# LCD_Daughterboard_v1_0.net
KiCad netlist of a schematic drawn in EAGLE
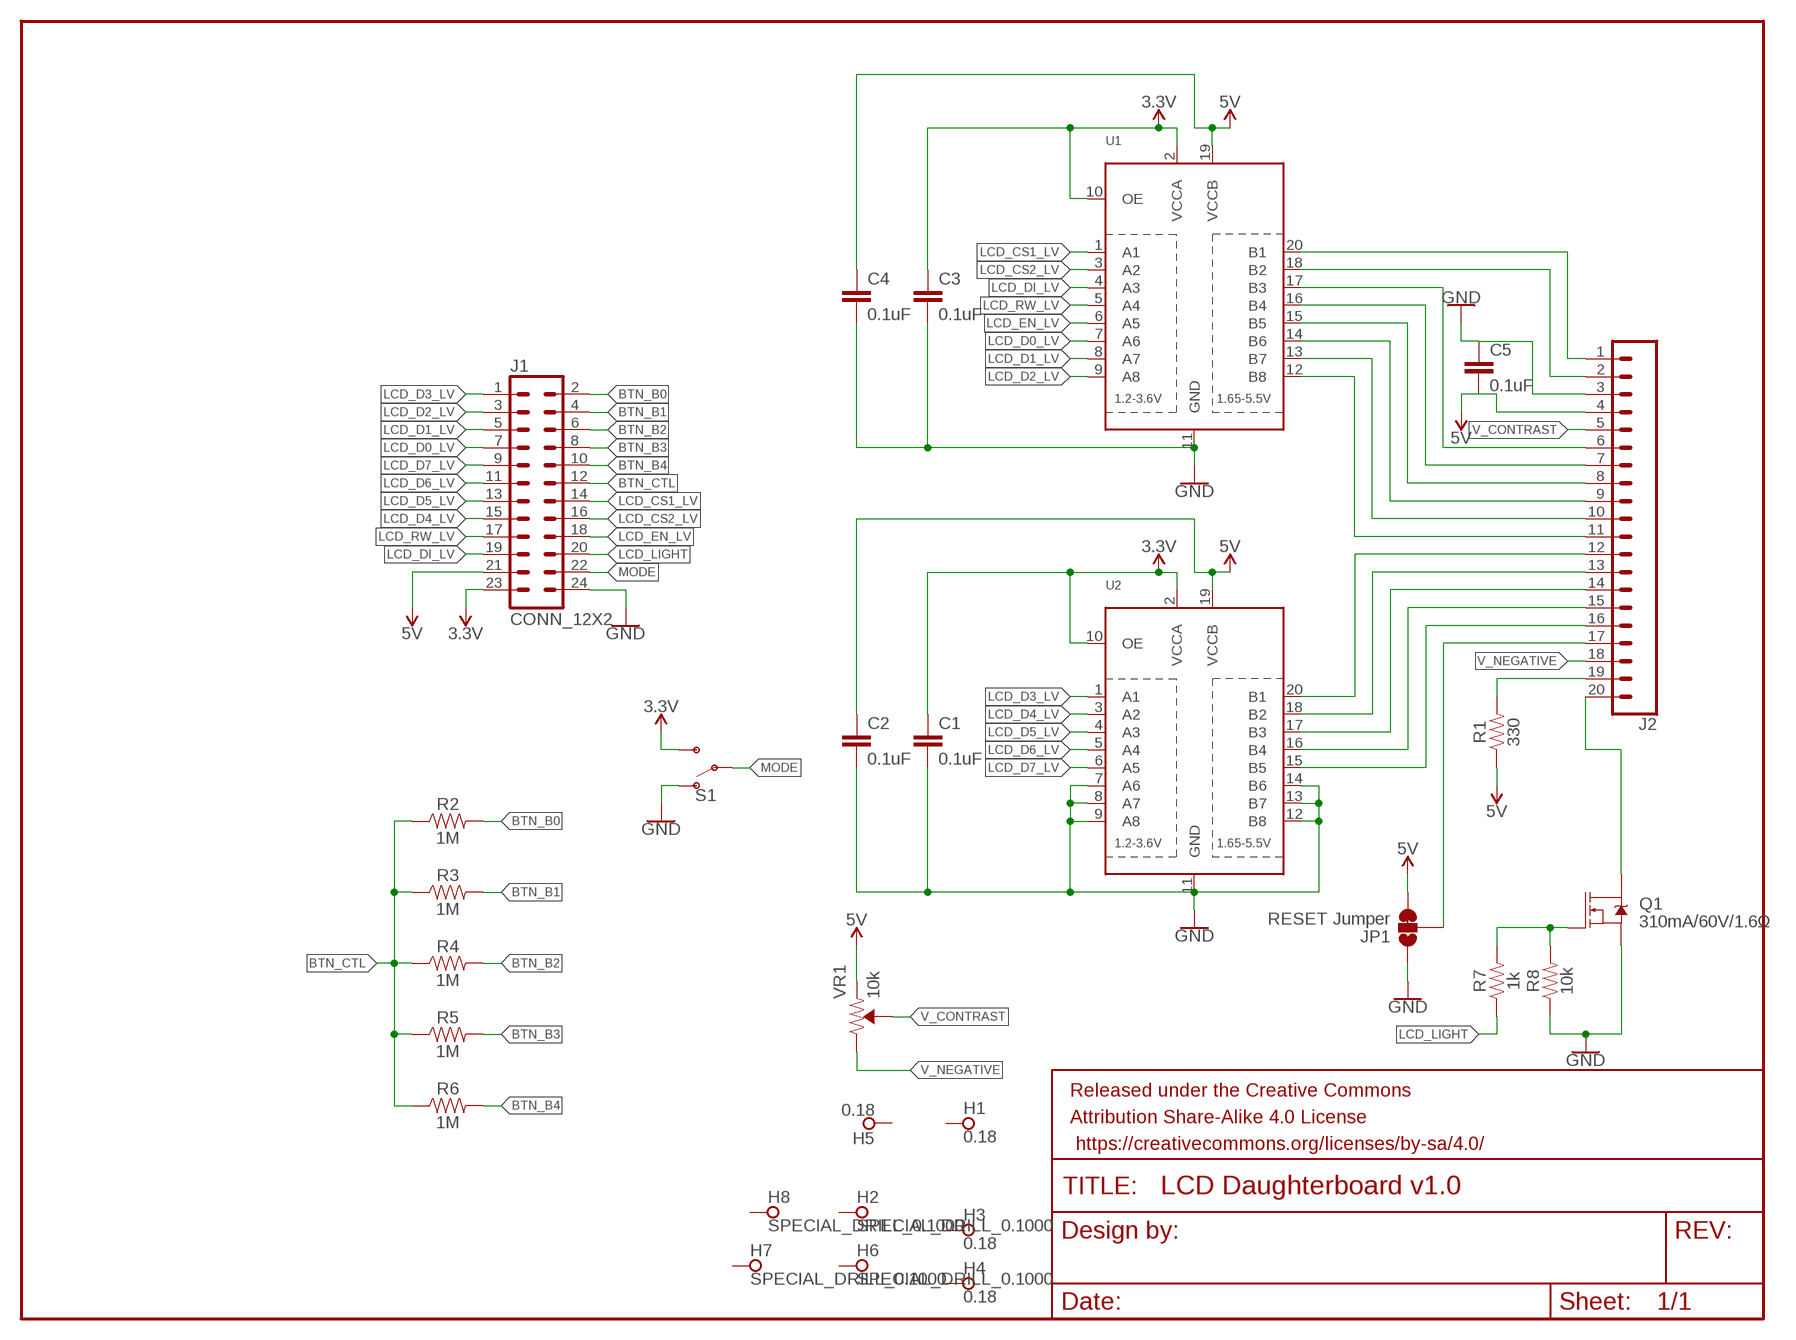
[diagram p0: schematic, sheet 1]

(export (version "E")
  (design (tool "Eeschema 10.0.6"))
  (components
    (comp (ref "C1")
      (value "0.1uF")
      (footprint "eagle-import:0603")
      (libsource (lib "eagle-import") (part "0.1UF-0603-25V-(+80/-20%)"))
    )
    (comp (ref "C2")
      (value "0.1uF")
      (footprint "eagle-import:0603")
      (libsource (lib "eagle-import") (part "0.1UF-0603-25V-(+80/-20%)"))
    )
    (comp (ref "C3")
      (value "0.1uF")
      (footprint "eagle-import:0603")
      (libsource (lib "eagle-import") (part "0.1UF-0603-25V-(+80/-20%)"))
    )
    (comp (ref "C4")
      (value "0.1uF")
      (footprint "eagle-import:0603")
      (libsource (lib "eagle-import") (part "0.1UF-0603-25V-(+80/-20%)"))
    )
    (comp (ref "C5")
      (value "0.1uF")
      (footprint "eagle-import:0603")
      (libsource (lib "eagle-import") (part "0.1UF-0603-25V-(+80/-20%)"))
    )
    (comp (ref "FRAME1")
      (value "FRAME-LETTERNO_PACKAGE")
      (footprint "eagle-import:DUMMY")
      (fields (field (name "DESIGNER") "Nobody"))
      (libsource (lib "eagle-import") (part "FRAME-LETTERNO_PACKAGE"))
    )
    (comp (ref "H1")
      (value "0.18")
      (footprint "eagle-import:PAD_0.1800")
      (libsource (lib "eagle-import") (part "SPECIAL_DRILL_0.1800"))
    )
    (comp (ref "H2")
      (value "SPECIAL_DRILL_0.1000")
      (footprint "eagle-import:PAD_0.1000")
      (libsource (lib "eagle-import") (part "SPECIAL_DRILL_0.1000"))
    )
    (comp (ref "H3")
      (value "0.18")
      (footprint "eagle-import:PAD_0.1800")
      (libsource (lib "eagle-import") (part "SPECIAL_DRILL_0.1800"))
    )
    (comp (ref "H4")
      (value "0.18")
      (footprint "eagle-import:PAD_0.1800")
      (libsource (lib "eagle-import") (part "SPECIAL_DRILL_0.1800"))
    )
    (comp (ref "H5")
      (value "0.18")
      (footprint "eagle-import:PAD_0.1800")
      (libsource (lib "eagle-import") (part "SPECIAL_DRILL_0.1800"))
    )
    (comp (ref "H6")
      (value "SPECIAL_DRILL_0.1000")
      (footprint "eagle-import:PAD_0.1000")
      (libsource (lib "eagle-import") (part "SPECIAL_DRILL_0.1000"))
    )
    (comp (ref "H7")
      (value "SPECIAL_DRILL_0.1000")
      (footprint "eagle-import:PAD_0.1000")
      (libsource (lib "eagle-import") (part "SPECIAL_DRILL_0.1000"))
    )
    (comp (ref "H8")
      (value "SPECIAL_DRILL_0.1000")
      (footprint "eagle-import:PAD_0.1000")
      (libsource (lib "eagle-import") (part "SPECIAL_DRILL_0.1000"))
    )
    (comp (ref "J1")
      (value "CONN_12X2")
      (footprint "eagle-import:2X12")
      (libsource (lib "eagle-import") (part "CONN_12X2"))
    )
    (comp (ref "J2")
      (value "CONN_20LOCK")
      (footprint "eagle-import:1X20_LOCK")
      (libsource (lib "eagle-import") (part "CONN_20LOCK"))
    )
    (comp (ref "JP1")
      (value "RESET Jumper")
      (footprint "eagle-import:SMT-JUMPER_3_1-NC_TRACE_SILK")
      (libsource (lib "eagle-import") (part "JUMPER-SMT_3_1-NC_TRACE_SILK"))
    )
    (comp (ref "Q1")
      (value "310mA/60V/1.6Ω")
      (footprint "eagle-import:SOT323")
      (libsource (lib "eagle-import") (part "MOSFET-NCH-2N7002PW"))
    )
    (comp (ref "R1")
      (value "330")
      (footprint "eagle-import:0603")
      (libsource (lib "eagle-import") (part "330OHM-0603-1/10W-1%"))
    )
    (comp (ref "R2")
      (value "1M")
      (footprint "eagle-import:0603")
      (libsource (lib "eagle-import") (part "1MOHM-0603-1/4W-5%"))
    )
    (comp (ref "R3")
      (value "1M")
      (footprint "eagle-import:0603")
      (libsource (lib "eagle-import") (part "1MOHM-0603-1/4W-5%"))
    )
    (comp (ref "R4")
      (value "1M")
      (footprint "eagle-import:0603")
      (libsource (lib "eagle-import") (part "1MOHM-0603-1/4W-5%"))
    )
    (comp (ref "R5")
      (value "1M")
      (footprint "eagle-import:0603")
      (libsource (lib "eagle-import") (part "1MOHM-0603-1/4W-5%"))
    )
    (comp (ref "R6")
      (value "1M")
      (footprint "eagle-import:0603")
      (libsource (lib "eagle-import") (part "1MOHM-0603-1/4W-5%"))
    )
    (comp (ref "R7")
      (value "1k")
      (footprint "eagle-import:0603")
      (libsource (lib "eagle-import") (part "1KOHM-0603-1/10W-1%"))
    )
    (comp (ref "R8")
      (value "10k")
      (footprint "eagle-import:0603")
      (libsource (lib "eagle-import") (part "10KOHM-0603-1/10W-1%"))
    )
    (comp (ref "S1")
      (value "SWITCH-SPDT-PTH-11.6X4.0MM")
      (footprint "eagle-import:SWITCH_SPDT_PTH_11.6X4.0MM")
      (libsource (lib "eagle-import") (part "SWITCH-SPDT-PTH-11.6X4.0MM"))
    )
    (comp (ref "U1")
      (value "TXB0108PWR")
      (footprint "eagle-import:TSSOP20")
      (libsource (lib "eagle-import") (part "TXB0108PWR"))
    )
    (comp (ref "U2")
      (value "TXB0108PWR")
      (footprint "eagle-import:TSSOP20")
      (libsource (lib "eagle-import") (part "TXB0108PWR"))
    )
    (comp (ref "VR1")
      (value "10k")
      (footprint "eagle-import:TRIMPOT-PTH-3386U")
      (libsource (lib "eagle-import") (part "TRIMPOT-PTH-10MM-KNOB-1/2W-10%"))
    )
  )
  (nets
    (net (code "1") (name "3.3V") (class "Default")
      (node (ref "C1") (pin "1") (pinfunction "1_1") (pintype "passive"))
      (node (ref "C3") (pin "1") (pinfunction "1_1") (pintype "passive"))
      (node (ref "J1") (pin "23") (pinfunction "23_23") (pintype "passive"))
      (node (ref "S1") (pin "3") (pinfunction "S_3") (pintype "passive"))
      (node (ref "U1") (pin "10") (pinfunction "OE_10") (pintype "bidirectional"))
      (node (ref "U1") (pin "2") (pinfunction "VCCA_2") (pintype "bidirectional"))
      (node (ref "U2") (pin "10") (pinfunction "OE_10") (pintype "bidirectional"))
      (node (ref "U2") (pin "2") (pinfunction "VCCA_2") (pintype "bidirectional"))
    )
    (net (code "2") (name "5V") (class "Default")
      (node (ref "C2") (pin "1") (pinfunction "1_1") (pintype "passive"))
      (node (ref "C4") (pin "1") (pinfunction "1_1") (pintype "passive"))
      (node (ref "C5") (pin "2") (pinfunction "2_2") (pintype "passive"))
      (node (ref "J1") (pin "21") (pinfunction "21_21") (pintype "passive"))
      (node (ref "J2") (pin "4") (pinfunction "4_4") (pintype "passive"))
      (node (ref "JP1") (pin "3") (pinfunction "3_3") (pintype "passive"))
      (node (ref "R1") (pin "1") (pinfunction "1_1") (pintype "passive"))
      (node (ref "U1") (pin "19") (pinfunction "VCCB_19") (pintype "bidirectional"))
      (node (ref "U2") (pin "19") (pinfunction "VCCB_19") (pintype "bidirectional"))
      (node (ref "VR1") (pin "1") (pinfunction "CCW_1") (pintype "passive"))
    )
    (net (code "3") (name "BTN_B0") (class "Default")
      (node (ref "J1") (pin "2") (pinfunction "2_2") (pintype "passive"))
      (node (ref "R2") (pin "2") (pinfunction "2_2") (pintype "passive"))
    )
    (net (code "4") (name "BTN_B1") (class "Default")
      (node (ref "J1") (pin "4") (pinfunction "4_4") (pintype "passive"))
      (node (ref "R3") (pin "2") (pinfunction "2_2") (pintype "passive"))
    )
    (net (code "5") (name "BTN_B2") (class "Default")
      (node (ref "J1") (pin "6") (pinfunction "6_6") (pintype "passive"))
      (node (ref "R4") (pin "2") (pinfunction "2_2") (pintype "passive"))
    )
    (net (code "6") (name "BTN_B3") (class "Default")
      (node (ref "J1") (pin "8") (pinfunction "8_8") (pintype "passive"))
      (node (ref "R5") (pin "2") (pinfunction "2_2") (pintype "passive"))
    )
    (net (code "7") (name "BTN_B4") (class "Default")
      (node (ref "J1") (pin "10") (pinfunction "10_10") (pintype "passive"))
      (node (ref "R6") (pin "2") (pinfunction "2_2") (pintype "passive"))
    )
    (net (code "8") (name "BTN_CTL") (class "Default")
      (node (ref "J1") (pin "12") (pinfunction "12_12") (pintype "passive"))
      (node (ref "R2") (pin "1") (pinfunction "1_1") (pintype "passive"))
      (node (ref "R3") (pin "1") (pinfunction "1_1") (pintype "passive"))
      (node (ref "R4") (pin "1") (pinfunction "1_1") (pintype "passive"))
      (node (ref "R5") (pin "1") (pinfunction "1_1") (pintype "passive"))
      (node (ref "R6") (pin "1") (pinfunction "1_1") (pintype "passive"))
    )
    (net (code "9") (name "GND") (class "Default")
      (node (ref "C1") (pin "2") (pinfunction "2_2") (pintype "passive"))
      (node (ref "C2") (pin "2") (pinfunction "2_2") (pintype "passive"))
      (node (ref "C3") (pin "2") (pinfunction "2_2") (pintype "passive"))
      (node (ref "C4") (pin "2") (pinfunction "2_2") (pintype "passive"))
      (node (ref "C5") (pin "1") (pinfunction "1_1") (pintype "passive"))
      (node (ref "J1") (pin "24") (pinfunction "24_24") (pintype "passive"))
      (node (ref "J2") (pin "3") (pinfunction "3_3") (pintype "passive"))
      (node (ref "JP1") (pin "1") (pinfunction "1_1") (pintype "passive"))
      (node (ref "Q1") (pin "2") (pinfunction "S_2") (pintype "bidirectional"))
      (node (ref "R8") (pin "1") (pinfunction "1_1") (pintype "passive"))
      (node (ref "S1") (pin "1") (pinfunction "O_1") (pintype "passive"))
      (node (ref "U1") (pin "11") (pinfunction "GND_11") (pintype "bidirectional"))
      (node (ref "U2") (pin "11") (pinfunction "GND_11") (pintype "bidirectional"))
      (node (ref "U2") (pin "12") (pinfunction "B8_12") (pintype "bidirectional"))
      (node (ref "U2") (pin "13") (pinfunction "B7_13") (pintype "bidirectional"))
      (node (ref "U2") (pin "14") (pinfunction "B6_14") (pintype "bidirectional"))
      (node (ref "U2") (pin "7") (pinfunction "A6_7") (pintype "bidirectional"))
      (node (ref "U2") (pin "8") (pinfunction "A7_8") (pintype "bidirectional"))
      (node (ref "U2") (pin "9") (pinfunction "A8_9") (pintype "bidirectional"))
    )
    (net (code "10") (name "LCD_CS1_LV") (class "Default")
      (node (ref "J1") (pin "14") (pinfunction "14_14") (pintype "passive"))
      (node (ref "U1") (pin "1") (pinfunction "A1_1") (pintype "bidirectional"))
    )
    (net (code "11") (name "LCD_CS2_LV") (class "Default")
      (node (ref "J1") (pin "16") (pinfunction "16_16") (pintype "passive"))
      (node (ref "U1") (pin "3") (pinfunction "A2_3") (pintype "bidirectional"))
    )
    (net (code "12") (name "LCD_D0_LV") (class "Default")
      (node (ref "J1") (pin "7") (pinfunction "7_7") (pintype "passive"))
      (node (ref "U1") (pin "7") (pinfunction "A6_7") (pintype "bidirectional"))
    )
    (net (code "13") (name "LCD_D1_LV") (class "Default")
      (node (ref "J1") (pin "5") (pinfunction "5_5") (pintype "passive"))
      (node (ref "U1") (pin "8") (pinfunction "A7_8") (pintype "bidirectional"))
    )
    (net (code "14") (name "LCD_D2_LV") (class "Default")
      (node (ref "J1") (pin "3") (pinfunction "3_3") (pintype "passive"))
      (node (ref "U1") (pin "9") (pinfunction "A8_9") (pintype "bidirectional"))
    )
    (net (code "15") (name "LCD_D3_LV") (class "Default")
      (node (ref "J1") (pin "1") (pinfunction "1_1") (pintype "passive"))
      (node (ref "U2") (pin "1") (pinfunction "A1_1") (pintype "bidirectional"))
    )
    (net (code "16") (name "LCD_D4_LV") (class "Default")
      (node (ref "J1") (pin "15") (pinfunction "15_15") (pintype "passive"))
      (node (ref "U2") (pin "3") (pinfunction "A2_3") (pintype "bidirectional"))
    )
    (net (code "17") (name "LCD_D5_LV") (class "Default")
      (node (ref "J1") (pin "13") (pinfunction "13_13") (pintype "passive"))
      (node (ref "U2") (pin "4") (pinfunction "A3_4") (pintype "bidirectional"))
    )
    (net (code "18") (name "LCD_D6_LV") (class "Default")
      (node (ref "J1") (pin "11") (pinfunction "11_11") (pintype "passive"))
      (node (ref "U2") (pin "5") (pinfunction "A4_5") (pintype "bidirectional"))
    )
    (net (code "19") (name "LCD_D7_LV") (class "Default")
      (node (ref "J1") (pin "9") (pinfunction "9_9") (pintype "passive"))
      (node (ref "U2") (pin "6") (pinfunction "A5_6") (pintype "bidirectional"))
    )
    (net (code "20") (name "LCD_DI_LV") (class "Default")
      (node (ref "J1") (pin "19") (pinfunction "19_19") (pintype "passive"))
      (node (ref "U1") (pin "4") (pinfunction "A3_4") (pintype "bidirectional"))
    )
    (net (code "21") (name "LCD_EN_LV") (class "Default")
      (node (ref "J1") (pin "18") (pinfunction "18_18") (pintype "passive"))
      (node (ref "U1") (pin "6") (pinfunction "A5_6") (pintype "bidirectional"))
    )
    (net (code "22") (name "LCD_LIGHT") (class "Default")
      (node (ref "J1") (pin "20") (pinfunction "20_20") (pintype "passive"))
      (node (ref "R7") (pin "1") (pinfunction "1_1") (pintype "passive"))
    )
    (net (code "23") (name "LCD_RW_LV") (class "Default")
      (node (ref "J1") (pin "17") (pinfunction "17_17") (pintype "passive"))
      (node (ref "U1") (pin "5") (pinfunction "A4_5") (pintype "bidirectional"))
    )
    (net (code "24") (name "MODE") (class "Default")
      (node (ref "J1") (pin "22") (pinfunction "22_22") (pintype "passive"))
      (node (ref "S1") (pin "2") (pinfunction "P_2") (pintype "passive"))
    )
    (net (code "25") (name "Net-(J2-Pad17)") (class "Default")
      (node (ref "J2") (pin "17") (pinfunction "17_17") (pintype "passive"))
      (node (ref "JP1") (pin "2") (pinfunction "2_2") (pintype "passive"))
    )
    (net (code "26") (name "Net-(J2-Pad19)") (class "Default")
      (node (ref "J2") (pin "19") (pinfunction "19_19") (pintype "passive"))
      (node (ref "R1") (pin "2") (pinfunction "2_2") (pintype "passive"))
    )
    (net (code "27") (name "Net-(Q1-D)") (class "Default")
      (node (ref "J2") (pin "20") (pinfunction "20_20") (pintype "passive"))
      (node (ref "Q1") (pin "3") (pinfunction "D_3") (pintype "bidirectional"))
    )
    (net (code "28") (name "Net-(Q1-G)") (class "Default")
      (node (ref "Q1") (pin "1") (pinfunction "G_1") (pintype "bidirectional"))
      (node (ref "R7") (pin "2") (pinfunction "2_2") (pintype "passive"))
      (node (ref "R8") (pin "2") (pinfunction "2_2") (pintype "passive"))
    )
    (net (code "29") (name "Net-(U1-B1)") (class "Default")
      (node (ref "J2") (pin "1") (pinfunction "1_1") (pintype "passive"))
      (node (ref "U1") (pin "20") (pinfunction "B1_20") (pintype "bidirectional"))
    )
    (net (code "30") (name "Net-(U1-B2)") (class "Default")
      (node (ref "J2") (pin "2") (pinfunction "2_2") (pintype "passive"))
      (node (ref "U1") (pin "18") (pinfunction "B2_18") (pintype "bidirectional"))
    )
    (net (code "31") (name "Net-(U1-B3)") (class "Default")
      (node (ref "J2") (pin "6") (pinfunction "6_6") (pintype "passive"))
      (node (ref "U1") (pin "17") (pinfunction "B3_17") (pintype "bidirectional"))
    )
    (net (code "32") (name "Net-(U1-B4)") (class "Default")
      (node (ref "J2") (pin "7") (pinfunction "7_7") (pintype "passive"))
      (node (ref "U1") (pin "16") (pinfunction "B4_16") (pintype "bidirectional"))
    )
    (net (code "33") (name "Net-(U1-B5)") (class "Default")
      (node (ref "J2") (pin "8") (pinfunction "8_8") (pintype "passive"))
      (node (ref "U1") (pin "15") (pinfunction "B5_15") (pintype "bidirectional"))
    )
    (net (code "34") (name "Net-(U1-B6)") (class "Default")
      (node (ref "J2") (pin "9") (pinfunction "9_9") (pintype "passive"))
      (node (ref "U1") (pin "14") (pinfunction "B6_14") (pintype "bidirectional"))
    )
    (net (code "35") (name "Net-(U1-B7)") (class "Default")
      (node (ref "J2") (pin "10") (pinfunction "10_10") (pintype "passive"))
      (node (ref "U1") (pin "13") (pinfunction "B7_13") (pintype "bidirectional"))
    )
    (net (code "36") (name "Net-(U1-B8)") (class "Default")
      (node (ref "J2") (pin "11") (pinfunction "11_11") (pintype "passive"))
      (node (ref "U1") (pin "12") (pinfunction "B8_12") (pintype "bidirectional"))
    )
    (net (code "37") (name "Net-(U2-B1)") (class "Default")
      (node (ref "J2") (pin "12") (pinfunction "12_12") (pintype "passive"))
      (node (ref "U2") (pin "20") (pinfunction "B1_20") (pintype "bidirectional"))
    )
    (net (code "38") (name "Net-(U2-B2)") (class "Default")
      (node (ref "J2") (pin "13") (pinfunction "13_13") (pintype "passive"))
      (node (ref "U2") (pin "18") (pinfunction "B2_18") (pintype "bidirectional"))
    )
    (net (code "39") (name "Net-(U2-B3)") (class "Default")
      (node (ref "J2") (pin "14") (pinfunction "14_14") (pintype "passive"))
      (node (ref "U2") (pin "17") (pinfunction "B3_17") (pintype "bidirectional"))
    )
    (net (code "40") (name "Net-(U2-B4)") (class "Default")
      (node (ref "J2") (pin "15") (pinfunction "15_15") (pintype "passive"))
      (node (ref "U2") (pin "16") (pinfunction "B4_16") (pintype "bidirectional"))
    )
    (net (code "41") (name "Net-(U2-B5)") (class "Default")
      (node (ref "J2") (pin "16") (pinfunction "16_16") (pintype "passive"))
      (node (ref "U2") (pin "15") (pinfunction "B5_15") (pintype "bidirectional"))
    )
    (net (code "42") (name "V_CONTRAST") (class "Default")
      (node (ref "J2") (pin "5") (pinfunction "5_5") (pintype "passive"))
      (node (ref "VR1") (pin "2") (pinfunction "WIPER_2") (pintype "passive"))
    )
    (net (code "43") (name "V_NEGATIVE") (class "Default")
      (node (ref "J2") (pin "18") (pinfunction "18_18") (pintype "passive"))
      (node (ref "VR1") (pin "3") (pinfunction "CW_3") (pintype "passive"))
    )
    (net (code "44") (name "unconnected-(H1-Pad1)") (class "Default")
      (node (ref "H1") (pin "1") (pinfunction "1_1") (pintype "passive"))
    )
    (net (code "45") (name "unconnected-(H2-Pad1)") (class "Default")
      (node (ref "H2") (pin "1") (pinfunction "1_1") (pintype "passive"))
    )
    (net (code "46") (name "unconnected-(H3-Pad1)") (class "Default")
      (node (ref "H3") (pin "1") (pinfunction "1_1") (pintype "passive"))
    )
    (net (code "47") (name "unconnected-(H4-Pad1)") (class "Default")
      (node (ref "H4") (pin "1") (pinfunction "1_1") (pintype "passive"))
    )
    (net (code "48") (name "unconnected-(H5-Pad1)") (class "Default")
      (node (ref "H5") (pin "1") (pinfunction "1_1") (pintype "passive"))
    )
    (net (code "49") (name "unconnected-(H6-Pad1)") (class "Default")
      (node (ref "H6") (pin "1") (pinfunction "1_1") (pintype "passive"))
    )
    (net (code "50") (name "unconnected-(H7-Pad1)") (class "Default")
      (node (ref "H7") (pin "1") (pinfunction "1_1") (pintype "passive"))
    )
    (net (code "51") (name "unconnected-(H8-Pad1)") (class "Default")
      (node (ref "H8") (pin "1") (pinfunction "1_1") (pintype "passive"))
    )
  )
)
